# main.net
KiCad netlist of a schematic drawn in Altium Designer
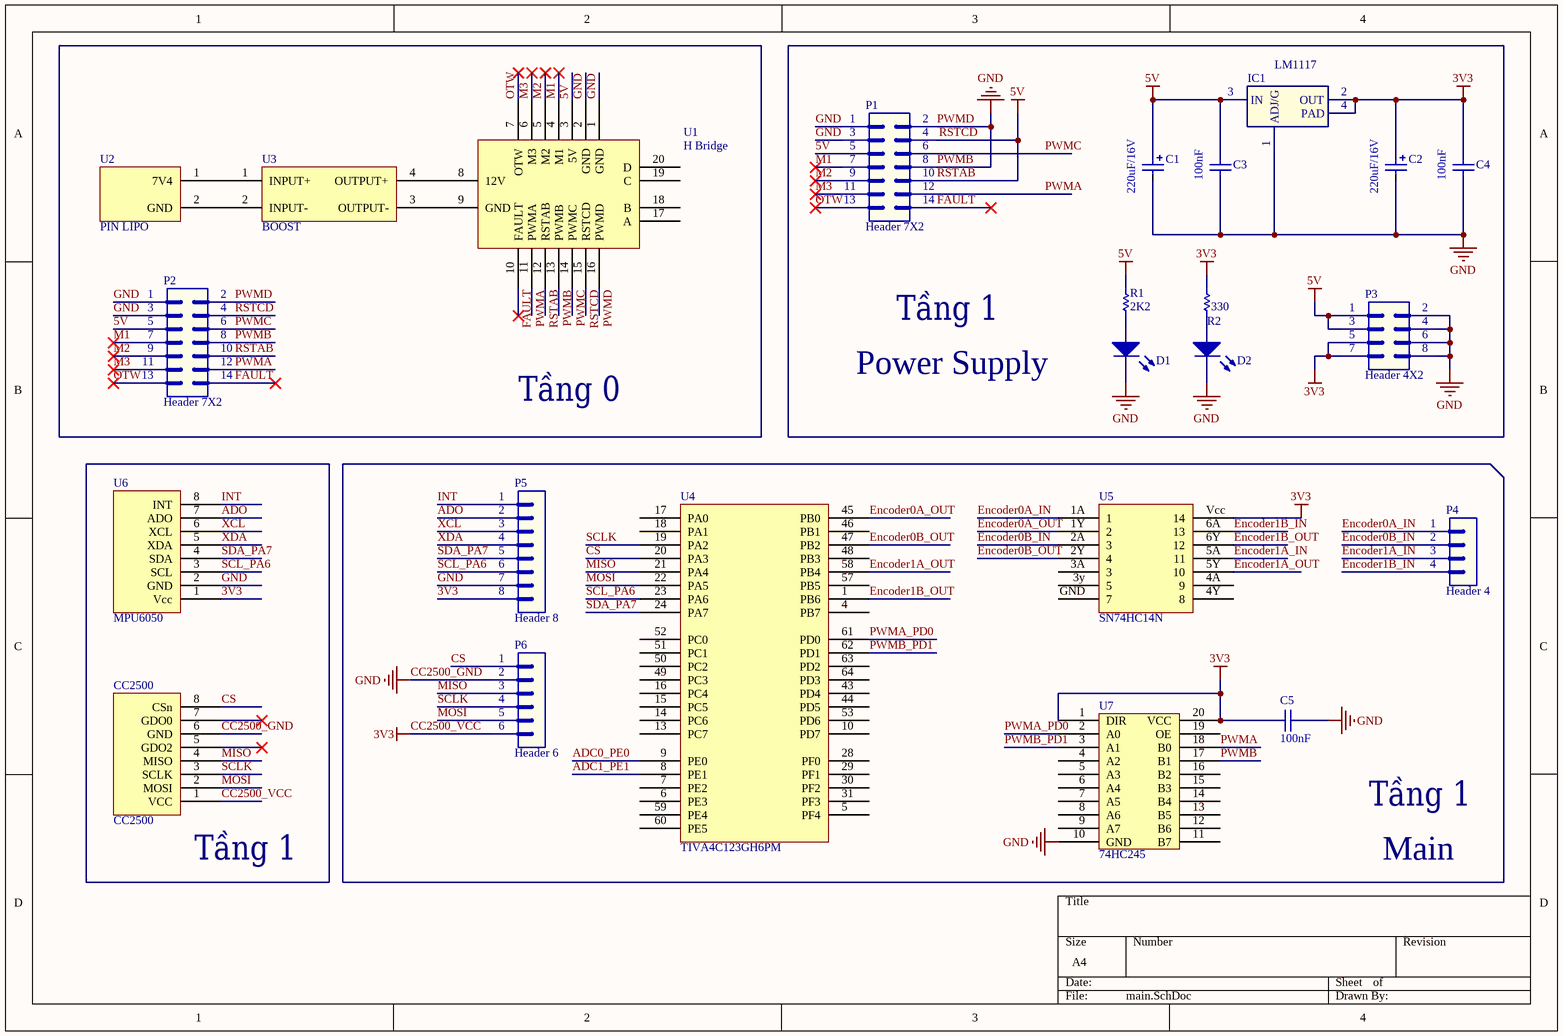
[diagram p0: main.SchDoc]

(export (version "E")
  (design (tool "Eeschema 10.0.6"))
  (components
    (comp (ref "C1")
      (value "220uF/16V")
      (footprint "CP1/2")
      (description "Polarized Capacitor (Radial)")
      (fields (field (name "Comment") "Cap Pol"))
      (libsource (lib "PIF_C16_lib") (part "Cap Pol"))
    )
    (comp (ref "C2")
      (value "220uF/16V")
      (footprint "CP1/2")
      (description "Polarized Capacitor (Radial)")
      (fields (field (name "Comment") "Cap Pol"))
      (libsource (lib "PIF_C16_lib") (part "Cap Pol"))
    )
    (comp (ref "C3")
      (value "100nF")
      (footprint "CN1")
      (description "Capacitor")
      (fields (field (name "Comment") "Cap Non-Pol"))
      (libsource (lib "PIF_C16_lib") (part "Cap Non-Pol"))
    )
    (comp (ref "C4")
      (value "100nF")
      (footprint "CN1")
      (description "Capacitor")
      (fields (field (name "Comment") "Cap Non-Pol"))
      (libsource (lib "PIF_C16_lib") (part "Cap Non-Pol"))
    )
    (comp (ref "C5")
      (value "100nF")
      (footprint "CN1")
      (description "Capacitor")
      (fields (field (name "Comment") "Cap Non-Pol"))
      (libsource (lib "PIF_C16_lib (2)") (part "Cap Non-Pol"))
    )
    (comp (ref "CC2500") (value "CC2500") (libsource (lib "CC2500") (part "CC2500")))
    (comp (ref "D1") (value "LED") (footprint "LED-5mm") (libsource (lib "PIF_C16_lib") (part "LED")))
    (comp (ref "D2") (value "LED") (footprint "LED-5mm") (libsource (lib "PIF_C16_lib") (part "LED")))
    (comp (ref "IC1")
      (value "LM1117")
      (footprint "SOT223-4N")
      (description "Available in 1.8V, 2.5V, 2.85V, 3.3V, 5V, and  Adjustable Versions")
      (libsource (lib "PIF_C16_lib") (part "LM1117"))
    )
    (comp (ref "P1")
      (value "Header 7X2")
      (footprint "JP7X2")
      (description "Header, 7-Pin, Dual row")
      (fields (field (name "PUBLISHER") "Altium Limited"))
      (libsource (lib "PIF_C16_lib (2)") (part "Header 7X2"))
    )
    (comp (ref "P2")
      (value "Header 7X2")
      (footprint "JP7X2")
      (description "Header, 7-Pin, Dual row")
      (fields (field (name "PUBLISHER") "Altium Limited"))
      (libsource (lib "PIF_C16_lib (2)") (part "Header 7X2"))
    )
    (comp (ref "P3")
      (value "Header 4X2")
      (footprint "JP4x2")
      (description "Header, 4-Pin, Dual row")
      (fields (field (name "PUBLISHER") "Altium Limited"))
      (libsource (lib "PIF_C16_lib (2)") (part "Header 4X2"))
    )
    (comp (ref "P4")
      (value "Header 4")
      (footprint "JP4")
      (description "Header, 4-Pin")
      (fields (field (name "PUBLISHER") "Altium Limited"))
      (libsource (lib "PIF_C16_lib (2)") (part "Header 4"))
    )
    (comp (ref "P5")
      (value "Header 8")
      (footprint "JP8")
      (description "Header, 8-Pin")
      (fields (field (name "PUBLISHER") "Altium Limited"))
      (libsource (lib "PIF_C16_lib (2)") (part "Header 8"))
    )
    (comp (ref "P6")
      (value "Header 6")
      (footprint "JP6")
      (description "Header, 6-Pin")
      (fields (field (name "PUBLISHER") "Altium Limited"))
      (libsource (lib "PIF_C16_lib (2)") (part "Header 6"))
    )
    (comp (ref "R1")
      (value "2K2")
      (footprint "RES 1/2W")
      (fields (field (name "Comment") "Resistor 1/4W"))
      (libsource (lib "PIF_C16_lib") (part "RES"))
    )
    (comp (ref "R2")
      (value "330")
      (footprint "RES 1/2W")
      (fields (field (name "Comment") "Resistor 1/4W"))
      (libsource (lib "PIF_C16_lib") (part "RES"))
    )
    (comp (ref "U1") (value "H Bridge") (libsource (lib "H_Bridge") (part "H Bridge")))
    (comp (ref "U2") (value "PIN LIPO") (libsource (lib "PIN LIPO") (part "PIN LIPO")))
    (comp (ref "U3") (value "BOOST") (libsource (lib "Boost") (part "BOOST")))
    (comp (ref "U4") (value "TIVA4C123GH6PM") (libsource (lib "TM4C123GH6PM") (part "TIVA4C123GH6PM")))
    (comp (ref "U5") (value "SN74HC14N") (libsource (lib "SN74HC14N") (part "SN74HC14N")))
    (comp (ref "U6") (value "MPU6050") (libsource (lib "MPU6050") (part "MPU6050")))
    (comp (ref "U7")
      (value "74HC245")
      (footprint "DIP20/W0.3")
      (description "Octal bus tranceiver")
      (libsource (lib "syhaunguyen") (part "74HC245"))
    )
  )
  (nets
    (net (code "1") (name "/ADC0_PE0") (class "Default")
      (node (ref "U4") (pin "9") (pinfunction "PE0_9") (pintype "passive"))
    )
    (net (code "2") (name "/ADC1_PE1") (class "Default")
      (node (ref "U4") (pin "8") (pinfunction "PE1_8") (pintype "passive"))
    )
    (net (code "3") (name "/ADO") (class "Default")
      (node (ref "P5") (pin "2") (pinfunction "2_2") (pintype "passive"))
      (node (ref "U6") (pin "7") (pinfunction "ADO_7") (pintype "passive"))
    )
    (net (code "4") (name "/CS") (class "Default")
      (node (ref "CC2500") (pin "8") (pinfunction "CSn_8") (pintype "passive"))
      (node (ref "P6") (pin "1") (pinfunction "1_1") (pintype "passive"))
      (node (ref "U4") (pin "20") (pinfunction "PA3_20") (pintype "passive"))
    )
    (net (code "5") (name "/Encoder0A_IN") (class "Default")
      (node (ref "P4") (pin "1") (pinfunction "1_1") (pintype "passive"))
      (node (ref "U5") (pin "1A") (pinfunction "1_1A") (pintype "passive"))
    )
    (net (code "6") (name "/Encoder0A_OUT") (class "Default")
      (node (ref "U4") (pin "45") (pinfunction "PB0_45") (pintype "passive"))
      (node (ref "U5") (pin "1Y") (pinfunction "2_1Y") (pintype "passive"))
    )
    (net (code "7") (name "/Encoder0B_IN") (class "Default")
      (node (ref "P4") (pin "2") (pinfunction "2_2") (pintype "passive"))
      (node (ref "U5") (pin "2A") (pinfunction "3_2A") (pintype "passive"))
    )
    (net (code "8") (name "/Encoder0B_OUT") (class "Default")
      (node (ref "U4") (pin "47") (pinfunction "PB2_47") (pintype "passive"))
      (node (ref "U5") (pin "2Y") (pinfunction "4_2Y") (pintype "passive"))
    )
    (net (code "9") (name "/Encoder1A_IN") (class "Default")
      (node (ref "P4") (pin "3") (pinfunction "3_3") (pintype "passive"))
      (node (ref "U5") (pin "5A") (pinfunction "11_5A") (pintype "passive"))
    )
    (net (code "10") (name "/Encoder1A_OUT") (class "Default")
      (node (ref "U4") (pin "58") (pinfunction "PB4_58") (pintype "passive"))
      (node (ref "U5") (pin "5Y") (pinfunction "10_5Y") (pintype "passive"))
    )
    (net (code "11") (name "/Encoder1B_IN") (class "Default")
      (node (ref "P4") (pin "4") (pinfunction "4_4") (pintype "passive"))
      (node (ref "U5") (pin "6A") (pinfunction "13_6A") (pintype "passive"))
    )
    (net (code "12") (name "/Encoder1B_OUT") (class "Default")
      (node (ref "U4") (pin "1") (pinfunction "PB6_1") (pintype "passive"))
      (node (ref "U5") (pin "6Y") (pinfunction "12_6Y") (pintype "passive"))
    )
    (net (code "13") (name "/FAULT") (class "Default")
      (node (ref "P1") (pin "14") (pinfunction "14_14") (pintype "passive"))
      (node (ref "P2") (pin "14") (pinfunction "14_14") (pintype "passive"))
      (node (ref "U1") (pin "10") (pinfunction "FAULT_10") (pintype "passive"))
    )
    (net (code "14") (name "/INT") (class "Default")
      (node (ref "P5") (pin "1") (pinfunction "1_1") (pintype "passive"))
      (node (ref "U6") (pin "8") (pinfunction "INT_8") (pintype "passive"))
    )
    (net (code "15") (name "/M1") (class "Default")
      (node (ref "P1") (pin "7") (pinfunction "7_7") (pintype "passive"))
      (node (ref "P2") (pin "7") (pinfunction "7_7") (pintype "passive"))
      (node (ref "U1") (pin "4") (pinfunction "M1_4") (pintype "passive"))
    )
    (net (code "16") (name "/M2") (class "Default")
      (node (ref "P1") (pin "9") (pinfunction "9_9") (pintype "passive"))
      (node (ref "P2") (pin "9") (pinfunction "9_9") (pintype "passive"))
      (node (ref "U1") (pin "5") (pinfunction "M2_5") (pintype "passive"))
    )
    (net (code "17") (name "/M3") (class "Default")
      (node (ref "P1") (pin "11") (pinfunction "11_11") (pintype "passive"))
      (node (ref "P2") (pin "11") (pinfunction "11_11") (pintype "passive"))
      (node (ref "U1") (pin "6") (pinfunction "M3_6") (pintype "passive"))
    )
    (net (code "18") (name "/MISO") (class "Default")
      (node (ref "CC2500") (pin "4") (pinfunction "MISO_4") (pintype "passive"))
      (node (ref "P6") (pin "3") (pinfunction "3_3") (pintype "passive"))
      (node (ref "U4") (pin "21") (pinfunction "PA4_21") (pintype "passive"))
    )
    (net (code "19") (name "/MOSI") (class "Default")
      (node (ref "CC2500") (pin "2") (pinfunction "MOSI_2") (pintype "passive"))
      (node (ref "P6") (pin "5") (pinfunction "5_5") (pintype "passive"))
      (node (ref "U4") (pin "22") (pinfunction "PA5_22") (pintype "passive"))
    )
    (net (code "20") (name "/OTW") (class "Default")
      (node (ref "P1") (pin "13") (pinfunction "13_13") (pintype "passive"))
      (node (ref "P2") (pin "13") (pinfunction "13_13") (pintype "passive"))
      (node (ref "U1") (pin "7") (pinfunction "OTW_7") (pintype "passive"))
    )
    (net (code "21") (name "/PWMA") (class "Default")
      (node (ref "P1") (pin "12") (pinfunction "12_12") (pintype "passive"))
      (node (ref "P2") (pin "12") (pinfunction "12_12") (pintype "passive"))
      (node (ref "U1") (pin "11") (pinfunction "PWMA_11") (pintype "passive"))
      (node (ref "U7") (pin "18") (pinfunction "B0_18") (pintype "passive"))
    )
    (net (code "22") (name "/PWMA_PD0") (class "Default")
      (node (ref "U4") (pin "61") (pinfunction "PD0_61") (pintype "passive"))
      (node (ref "U7") (pin "2") (pinfunction "A0_2") (pintype "passive"))
    )
    (net (code "23") (name "/PWMB_PD1") (class "Default")
      (node (ref "U4") (pin "62") (pinfunction "PD1_62") (pintype "passive"))
      (node (ref "U7") (pin "3") (pinfunction "A1_3") (pintype "passive"))
    )
    (net (code "24") (name "/PWMC") (class "Default")
      (node (ref "P1") (pin "6") (pinfunction "6_6") (pintype "passive"))
      (node (ref "P2") (pin "6") (pinfunction "6_6") (pintype "passive"))
      (node (ref "U1") (pin "14") (pinfunction "PWMC_14") (pintype "passive"))
    )
    (net (code "25") (name "/SCLK") (class "Default")
      (node (ref "CC2500") (pin "3") (pinfunction "SCLK_3") (pintype "passive"))
      (node (ref "P6") (pin "4") (pinfunction "4_4") (pintype "passive"))
      (node (ref "U4") (pin "19") (pinfunction "PA2_19") (pintype "passive"))
    )
    (net (code "26") (name "/SCL_PA6") (class "Default")
      (node (ref "P5") (pin "6") (pinfunction "6_6") (pintype "passive"))
      (node (ref "U4") (pin "23") (pinfunction "PA6_23") (pintype "passive"))
      (node (ref "U6") (pin "3") (pinfunction "SCL_3") (pintype "passive"))
    )
    (net (code "27") (name "/SDA_PA7") (class "Default")
      (node (ref "P5") (pin "5") (pinfunction "5_5") (pintype "passive"))
      (node (ref "U4") (pin "24") (pinfunction "PA7_24") (pintype "passive"))
      (node (ref "U6") (pin "4") (pinfunction "SDA_4") (pintype "passive"))
    )
    (net (code "28") (name "/XCL") (class "Default")
      (node (ref "P5") (pin "3") (pinfunction "3_3") (pintype "passive"))
      (node (ref "U6") (pin "6") (pinfunction "XCL_6") (pintype "passive"))
    )
    (net (code "29") (name "/XDA") (class "Default")
      (node (ref "P5") (pin "4") (pinfunction "4_4") (pintype "passive"))
      (node (ref "U6") (pin "5") (pinfunction "XDA_5") (pintype "passive"))
    )
    (net (code "30") (name "3V3") (class "Default")
      (node (ref "C2") (pin "1") (pinfunction "1_1") (pintype "passive"))
      (node (ref "C4") (pin "2") (pinfunction "2_2") (pintype "passive"))
      (node (ref "C5") (pin "1") (pinfunction "1_1") (pintype "passive"))
      (node (ref "CC2500") (pin "1") (pinfunction "VCC_1") (pintype "passive"))
      (node (ref "IC1") (pin "2") (pinfunction "OUT_2") (pintype "passive"))
      (node (ref "IC1") (pin "4") (pinfunction "PAD_4") (pintype "passive"))
      (node (ref "P3") (pin "5") (pinfunction "5_5") (pintype "passive"))
      (node (ref "P3") (pin "7") (pinfunction "7_7") (pintype "passive"))
      (node (ref "P5") (pin "8") (pinfunction "8_8") (pintype "passive"))
      (node (ref "P6") (pin "6") (pinfunction "6_6") (pintype "passive"))
      (node (ref "R2") (pin "2") (pintype "passive"))
      (node (ref "U5") (pin "Vcc") (pinfunction "14_Vcc") (pintype "passive"))
      (node (ref "U6") (pin "1") (pinfunction "Vcc_1") (pintype "passive"))
      (node (ref "U7") (pin "1") (pinfunction "DIR_1") (pintype "passive"))
      (node (ref "U7") (pin "20") (pinfunction "VCC_20") (pintype "power_in"))
    )
    (net (code "31") (name "5V") (class "Default")
      (node (ref "C1") (pin "1") (pinfunction "1_1") (pintype "passive"))
      (node (ref "C3") (pin "2") (pinfunction "2_2") (pintype "passive"))
      (node (ref "IC1") (pin "3") (pinfunction "IN_3") (pintype "passive"))
      (node (ref "P1") (pin "10") (pinfunction "10_10") (pintype "passive"))
      (node (ref "P1") (pin "4") (pinfunction "4_4") (pintype "passive"))
      (node (ref "P1") (pin "5") (pinfunction "5_5") (pintype "passive"))
      (node (ref "P2") (pin "10") (pinfunction "10_10") (pintype "passive"))
      (node (ref "P2") (pin "4") (pinfunction "4_4") (pintype "passive"))
      (node (ref "P2") (pin "5") (pinfunction "5_5") (pintype "passive"))
      (node (ref "P3") (pin "1") (pinfunction "1_1") (pintype "passive"))
      (node (ref "P3") (pin "3") (pinfunction "3_3") (pintype "passive"))
      (node (ref "R1") (pin "2") (pintype "passive"))
      (node (ref "U1") (pin "12") (pinfunction "RSTAB_12") (pintype "passive"))
      (node (ref "U1") (pin "15") (pinfunction "RSTCD_15") (pintype "passive"))
      (node (ref "U1") (pin "3") (pinfunction "5V_3") (pintype "passive"))
    )
    (net (code "32") (name "GND") (class "Default")
      (node (ref "C1") (pin "2") (pinfunction "2_2") (pintype "passive"))
      (node (ref "C2") (pin "2") (pinfunction "2_2") (pintype "passive"))
      (node (ref "C3") (pin "1") (pinfunction "1_1") (pintype "passive"))
      (node (ref "C4") (pin "1") (pinfunction "1_1") (pintype "passive"))
      (node (ref "C5") (pin "2") (pinfunction "2_2") (pintype "passive"))
      (node (ref "CC2500") (pin "6") (pinfunction "GND_6") (pintype "passive"))
      (node (ref "D1") (pin "2") (pinfunction "K_2") (pintype "passive"))
      (node (ref "D2") (pin "2") (pinfunction "K_2") (pintype "passive"))
      (node (ref "IC1") (pin "1") (pinfunction "ADJ/G_1") (pintype "passive"))
      (node (ref "P1") (pin "1") (pinfunction "1_1") (pintype "passive"))
      (node (ref "P1") (pin "2") (pinfunction "2_2") (pintype "passive"))
      (node (ref "P1") (pin "3") (pinfunction "3_3") (pintype "passive"))
      (node (ref "P1") (pin "8") (pinfunction "8_8") (pintype "passive"))
      (node (ref "P2") (pin "1") (pinfunction "1_1") (pintype "passive"))
      (node (ref "P2") (pin "2") (pinfunction "2_2") (pintype "passive"))
      (node (ref "P2") (pin "3") (pinfunction "3_3") (pintype "passive"))
      (node (ref "P2") (pin "8") (pinfunction "8_8") (pintype "passive"))
      (node (ref "P3") (pin "2") (pinfunction "2_2") (pintype "passive"))
      (node (ref "P3") (pin "4") (pinfunction "4_4") (pintype "passive"))
      (node (ref "P3") (pin "6") (pinfunction "6_6") (pintype "passive"))
      (node (ref "P3") (pin "8") (pinfunction "8_8") (pintype "passive"))
      (node (ref "P5") (pin "7") (pinfunction "7_7") (pintype "passive"))
      (node (ref "P6") (pin "2") (pinfunction "2_2") (pintype "passive"))
      (node (ref "U1") (pin "1") (pinfunction "GND_1") (pintype "passive"))
      (node (ref "U1") (pin "13") (pinfunction "PWMB_13") (pintype "passive"))
      (node (ref "U1") (pin "16") (pinfunction "PWMD_16") (pintype "passive"))
      (node (ref "U1") (pin "2") (pinfunction "GND_2") (pintype "passive"))
      (node (ref "U6") (pin "2") (pinfunction "GND_2") (pintype "passive"))
      (node (ref "U7") (pin "10") (pinfunction "GND_10") (pintype "power_in"))
      (node (ref "U7") (pin "17") (pinfunction "B1_17") (pintype "passive"))
    )
    (net (code "33") (name "Net-(D1-A)") (class "Default")
      (node (ref "D1") (pin "1") (pinfunction "A_1") (pintype "passive"))
      (node (ref "R1") (pin "1") (pintype "passive"))
    )
    (net (code "34") (name "Net-(D2-A)") (class "Default")
      (node (ref "D2") (pin "1") (pinfunction "A_1") (pintype "passive"))
      (node (ref "R2") (pin "1") (pintype "passive"))
    )
    (net (code "35") (name "Net-(U1-12V)") (class "Default")
      (node (ref "U1") (pin "8") (pinfunction "12V_8") (pintype "passive"))
      (node (ref "U3") (pin "4") (pinfunction "OUTPUT+_4") (pintype "passive"))
    )
    (net (code "36") (name "Net-(U2-7V4)") (class "Default")
      (node (ref "U2") (pin "1") (pinfunction "7V4_1") (pintype "passive"))
      (node (ref "U3") (pin "1") (pinfunction "INPUT+_1") (pintype "passive"))
    )
    (net (code "37") (name "Net-(U2-GND)") (class "Default")
      (node (ref "U2") (pin "2") (pinfunction "GND_2") (pintype "passive"))
      (node (ref "U3") (pin "2") (pinfunction "INPUT-_2") (pintype "passive"))
    )
    (net (code "38") (name "Net-(U3-OUTPUT-)") (class "Default")
      (node (ref "U1") (pin "9") (pinfunction "GND_9") (pintype "passive"))
      (node (ref "U3") (pin "3") (pinfunction "OUTPUT-_3") (pintype "passive"))
    )
    (net (code "39") (name "unconnected-(CC2500-GDO0-Pad7)") (class "Default")
      (node (ref "CC2500") (pin "7") (pinfunction "GDO0_7") (pintype "passive+no_connect"))
    )
    (net (code "40") (name "unconnected-(CC2500-GDO2-Pad5)") (class "Default")
      (node (ref "CC2500") (pin "5") (pinfunction "GDO2_5") (pintype "passive+no_connect"))
    )
    (net (code "41") (name "unconnected-(U1-A-Pad17)") (class "Default")
      (node (ref "U1") (pin "17") (pinfunction "A_17") (pintype "passive"))
    )
    (net (code "42") (name "unconnected-(U1-B-Pad18)") (class "Default")
      (node (ref "U1") (pin "18") (pinfunction "B_18") (pintype "passive"))
    )
    (net (code "43") (name "unconnected-(U1-C-Pad19)") (class "Default")
      (node (ref "U1") (pin "19") (pinfunction "C_19") (pintype "passive"))
    )
    (net (code "44") (name "unconnected-(U1-D-Pad20)") (class "Default")
      (node (ref "U1") (pin "20") (pinfunction "D_20") (pintype "passive"))
    )
    (net (code "45") (name "unconnected-(U4-PA0-Pad17)") (class "Default")
      (node (ref "U4") (pin "17") (pinfunction "PA0_17") (pintype "passive"))
    )
    (net (code "46") (name "unconnected-(U4-PA1-Pad18)") (class "Default")
      (node (ref "U4") (pin "18") (pinfunction "PA1_18") (pintype "passive"))
    )
    (net (code "47") (name "unconnected-(U4-PB1-Pad46)") (class "Default")
      (node (ref "U4") (pin "46") (pinfunction "PB1_46") (pintype "passive"))
    )
    (net (code "48") (name "unconnected-(U4-PB3-Pad48)") (class "Default")
      (node (ref "U4") (pin "48") (pinfunction "PB3_48") (pintype "passive"))
    )
    (net (code "49") (name "unconnected-(U4-PB5-Pad57)") (class "Default")
      (node (ref "U4") (pin "57") (pinfunction "PB5_57") (pintype "passive"))
    )
    (net (code "50") (name "unconnected-(U4-PB7-Pad4)") (class "Default")
      (node (ref "U4") (pin "4") (pinfunction "PB7_4") (pintype "passive"))
    )
    (net (code "51") (name "unconnected-(U4-PC0-Pad52)") (class "Default")
      (node (ref "U4") (pin "52") (pinfunction "PC0_52") (pintype "passive"))
    )
    (net (code "52") (name "unconnected-(U4-PC1-Pad51)") (class "Default")
      (node (ref "U4") (pin "51") (pinfunction "PC1_51") (pintype "passive"))
    )
    (net (code "53") (name "unconnected-(U4-PC2-Pad50)") (class "Default")
      (node (ref "U4") (pin "50") (pinfunction "PC2_50") (pintype "passive"))
    )
    (net (code "54") (name "unconnected-(U4-PC3-Pad49)") (class "Default")
      (node (ref "U4") (pin "49") (pinfunction "PC3_49") (pintype "passive"))
    )
    (net (code "55") (name "unconnected-(U4-PC4-Pad16)") (class "Default")
      (node (ref "U4") (pin "16") (pinfunction "PC4_16") (pintype "passive"))
    )
    (net (code "56") (name "unconnected-(U4-PC5-Pad15)") (class "Default")
      (node (ref "U4") (pin "15") (pinfunction "PC5_15") (pintype "passive"))
    )
    (net (code "57") (name "unconnected-(U4-PC6-Pad14)") (class "Default")
      (node (ref "U4") (pin "14") (pinfunction "PC6_14") (pintype "passive"))
    )
    (net (code "58") (name "unconnected-(U4-PC7-Pad13)") (class "Default")
      (node (ref "U4") (pin "13") (pinfunction "PC7_13") (pintype "passive"))
    )
    (net (code "59") (name "unconnected-(U4-PD2-Pad63)") (class "Default")
      (node (ref "U4") (pin "63") (pinfunction "PD2_63") (pintype "passive"))
    )
    (net (code "60") (name "unconnected-(U4-PD3-Pad64)") (class "Default")
      (node (ref "U4") (pin "64") (pinfunction "PD3_64") (pintype "passive"))
    )
    (net (code "61") (name "unconnected-(U4-PD4-Pad43)") (class "Default")
      (node (ref "U4") (pin "43") (pinfunction "PD4_43") (pintype "passive"))
    )
    (net (code "62") (name "unconnected-(U4-PD5-Pad44)") (class "Default")
      (node (ref "U4") (pin "44") (pinfunction "PD5_44") (pintype "passive"))
    )
    (net (code "63") (name "unconnected-(U4-PD6-Pad53)") (class "Default")
      (node (ref "U4") (pin "53") (pinfunction "PD6_53") (pintype "passive"))
    )
    (net (code "64") (name "unconnected-(U4-PD7-Pad10)") (class "Default")
      (node (ref "U4") (pin "10") (pinfunction "PD7_10") (pintype "passive"))
    )
    (net (code "65") (name "unconnected-(U4-PE2-Pad7)") (class "Default")
      (node (ref "U4") (pin "7") (pinfunction "PE2_7") (pintype "passive"))
    )
    (net (code "66") (name "unconnected-(U4-PE3-Pad6)") (class "Default")
      (node (ref "U4") (pin "6") (pinfunction "PE3_6") (pintype "passive"))
    )
    (net (code "67") (name "unconnected-(U4-PE4-Pad59)") (class "Default")
      (node (ref "U4") (pin "59") (pinfunction "PE4_59") (pintype "passive"))
    )
    (net (code "68") (name "unconnected-(U4-PE5-Pad60)") (class "Default")
      (node (ref "U4") (pin "60") (pinfunction "PE5_60") (pintype "passive"))
    )
    (net (code "69") (name "unconnected-(U4-PF0-Pad28)") (class "Default")
      (node (ref "U4") (pin "28") (pinfunction "PF0_28") (pintype "passive"))
    )
    (net (code "70") (name "unconnected-(U4-PF1-Pad29)") (class "Default")
      (node (ref "U4") (pin "29") (pinfunction "PF1_29") (pintype "passive"))
    )
    (net (code "71") (name "unconnected-(U4-PF2-Pad30)") (class "Default")
      (node (ref "U4") (pin "30") (pinfunction "PF2_30") (pintype "passive"))
    )
    (net (code "72") (name "unconnected-(U4-PF3-Pad31)") (class "Default")
      (node (ref "U4") (pin "31") (pinfunction "PF3_31") (pintype "passive"))
    )
    (net (code "73") (name "unconnected-(U4-PF4-Pad5)") (class "Default")
      (node (ref "U4") (pin "5") (pinfunction "PF4_5") (pintype "passive"))
    )
    (net (code "74") (name "unconnected-(U5-3-Pad3A)") (class "Default")
      (node (ref "U5") (pin "3A") (pinfunction "3_3A") (pintype "passive"))
    )
    (net (code "75") (name "unconnected-(U5-5-Pad3y)") (class "Default")
      (node (ref "U5") (pin "3y") (pinfunction "5_3y") (pintype "passive"))
    )
    (net (code "76") (name "unconnected-(U5-7-PadGND)") (class "Default")
      (node (ref "U5") (pin "GND") (pinfunction "7_GND") (pintype "passive"))
    )
    (net (code "77") (name "unconnected-(U5-8-Pad4Y)") (class "Default")
      (node (ref "U5") (pin "4Y") (pinfunction "8_4Y") (pintype "passive"))
    )
    (net (code "78") (name "unconnected-(U5-9-Pad4A)") (class "Default")
      (node (ref "U5") (pin "4A") (pinfunction "9_4A") (pintype "passive"))
    )
    (net (code "79") (name "unconnected-(U7-A2-Pad4)") (class "Default")
      (node (ref "U7") (pin "4") (pinfunction "A2_4") (pintype "passive"))
    )
    (net (code "80") (name "unconnected-(U7-A3-Pad5)") (class "Default")
      (node (ref "U7") (pin "5") (pinfunction "A3_5") (pintype "passive"))
    )
    (net (code "81") (name "unconnected-(U7-A4-Pad6)") (class "Default")
      (node (ref "U7") (pin "6") (pinfunction "A4_6") (pintype "passive"))
    )
    (net (code "82") (name "unconnected-(U7-A5-Pad7)") (class "Default")
      (node (ref "U7") (pin "7") (pinfunction "A5_7") (pintype "passive"))
    )
    (net (code "83") (name "unconnected-(U7-A6-Pad8)") (class "Default")
      (node (ref "U7") (pin "8") (pinfunction "A6_8") (pintype "passive"))
    )
    (net (code "84") (name "unconnected-(U7-A7-Pad9)") (class "Default")
      (node (ref "U7") (pin "9") (pinfunction "A7_9") (pintype "passive"))
    )
    (net (code "85") (name "unconnected-(U7-B2-Pad16)") (class "Default")
      (node (ref "U7") (pin "16") (pinfunction "B2_16") (pintype "passive"))
    )
    (net (code "86") (name "unconnected-(U7-B3-Pad15)") (class "Default")
      (node (ref "U7") (pin "15") (pinfunction "B3_15") (pintype "passive"))
    )
    (net (code "87") (name "unconnected-(U7-B4-Pad14)") (class "Default")
      (node (ref "U7") (pin "14") (pinfunction "B4_14") (pintype "passive"))
    )
    (net (code "88") (name "unconnected-(U7-B5-Pad13)") (class "Default")
      (node (ref "U7") (pin "13") (pinfunction "B5_13") (pintype "passive"))
    )
    (net (code "89") (name "unconnected-(U7-B6-Pad12)") (class "Default")
      (node (ref "U7") (pin "12") (pinfunction "B6_12") (pintype "passive"))
    )
    (net (code "90") (name "unconnected-(U7-B7-Pad11)") (class "Default")
      (node (ref "U7") (pin "11") (pinfunction "B7_11") (pintype "passive"))
    )
    (net (code "91") (name "unconnected-(U7-OE-Pad19)") (class "Default")
      (node (ref "U7") (pin "19") (pinfunction "OE_19") (pintype "passive"))
    )
  )
)
